# rgb2hdmi-composite-adapter.net
KiCad netlist of a schematic drawn in EAGLE
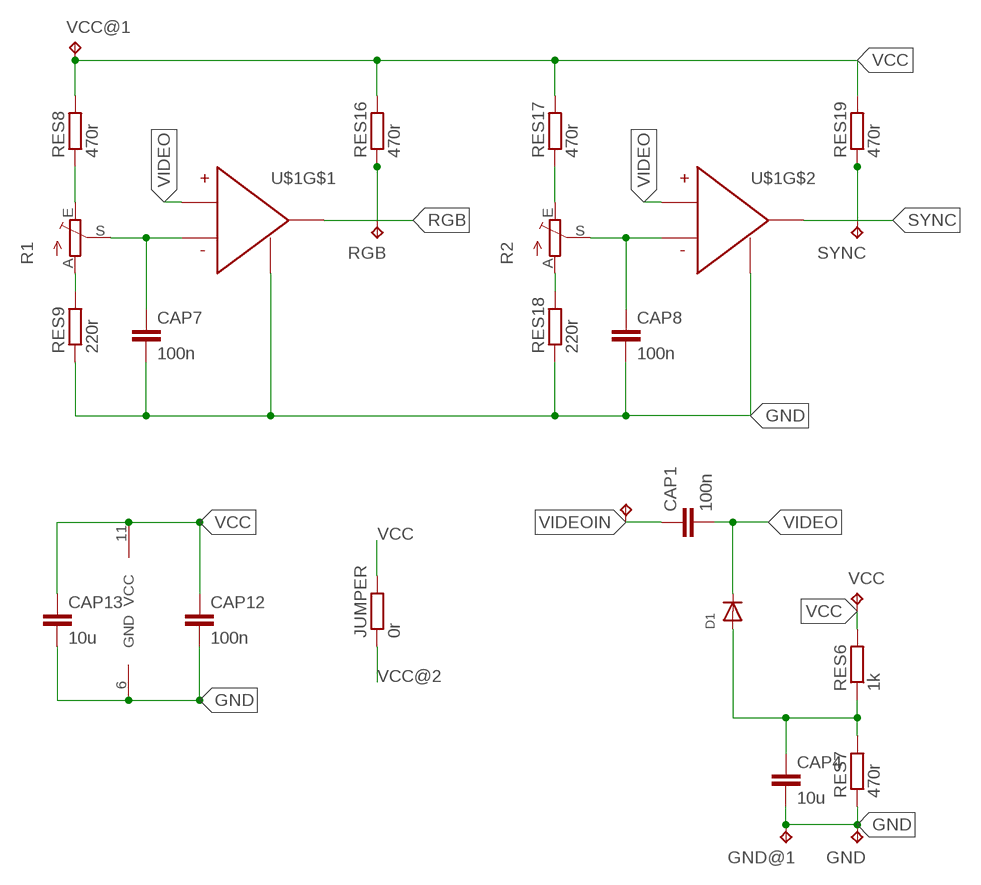
[diagram p0: schematic, sheet 1]

(export (version "E")
  (design (tool "Eeschema 10.0.6"))
  (components
    (comp (ref "CAP1")
      (value "100n")
      (footprint "eagle-import:C025-025X050")
      (libsource (lib "eagle-import") (part "C-EU025-025X050"))
    )
    (comp (ref "CAP4")
      (value "10u")
      (footprint "eagle-import:C025-025X050")
      (libsource (lib "eagle-import") (part "C-EU025-025X050"))
    )
    (comp (ref "CAP7")
      (value "100n")
      (footprint "eagle-import:C025-025X050")
      (libsource (lib "eagle-import") (part "C-EU025-025X050"))
    )
    (comp (ref "CAP8")
      (value "100n")
      (footprint "eagle-import:C025-025X050")
      (libsource (lib "eagle-import") (part "C-EU025-025X050"))
    )
    (comp (ref "CAP12")
      (value "100n")
      (footprint "eagle-import:C025-025X050")
      (libsource (lib "eagle-import") (part "C-EU025-025X050"))
    )
    (comp (ref "CAP13")
      (value "10u")
      (footprint "eagle-import:C025-025X050")
      (libsource (lib "eagle-import") (part "C-EU025-025X050"))
    )
    (comp (ref "D1")
      (value "DIODEDO-1N4148")
      (footprint "eagle-import:DO-1N4148")
      (libsource (lib "eagle-import") (part "DIODEDO-1N4148"))
    )
    (comp (ref "GND")
      (value "TPPAD1-17Y")
      (footprint "eagle-import:P1-17Y")
      (libsource (lib "eagle-import") (part "TPPAD1-17Y"))
    )
    (comp (ref "GND@1")
      (value "TPPAD1-17Y")
      (footprint "eagle-import:P1-17Y")
      (libsource (lib "eagle-import") (part "TPPAD1-17Y"))
    )
    (comp (ref "JUMPER")
      (value "0r")
      (footprint "eagle-import:0207_10")
      (libsource (lib "eagle-import") (part "R-EU_0207/10"))
    )
    (comp (ref "R1")
      (value "TRIM_EU-B64Y")
      (footprint "eagle-import:B64Y")
      (libsource (lib "eagle-import") (part "TRIM_EU-B64Y"))
    )
    (comp (ref "R2")
      (value "TRIM_EU-B64Y")
      (footprint "eagle-import:B64Y")
      (libsource (lib "eagle-import") (part "TRIM_EU-B64Y"))
    )
    (comp (ref "RES6")
      (value "1k")
      (footprint "eagle-import:0207_10")
      (libsource (lib "eagle-import") (part "R-EU_0207/10"))
    )
    (comp (ref "RES7")
      (value "470r")
      (footprint "eagle-import:0207_10")
      (libsource (lib "eagle-import") (part "R-EU_0207/10"))
    )
    (comp (ref "RES8")
      (value "470r")
      (footprint "eagle-import:0207_10")
      (libsource (lib "eagle-import") (part "R-EU_0207/10"))
    )
    (comp (ref "RES9")
      (value "220r")
      (footprint "eagle-import:0207_10")
      (libsource (lib "eagle-import") (part "R-EU_0207/10"))
    )
    (comp (ref "RES16")
      (value "470r")
      (footprint "eagle-import:0207_10")
      (libsource (lib "eagle-import") (part "R-EU_0207/10"))
    )
    (comp (ref "RES17")
      (value "470r")
      (footprint "eagle-import:0207_10")
      (libsource (lib "eagle-import") (part "R-EU_0207/10"))
    )
    (comp (ref "RES18")
      (value "220r")
      (footprint "eagle-import:0207_10")
      (libsource (lib "eagle-import") (part "R-EU_0207/10"))
    )
    (comp (ref "RES19")
      (value "470r")
      (footprint "eagle-import:0207_10")
      (libsource (lib "eagle-import") (part "R-EU_0207/10"))
    )
    (comp (ref "RGB")
      (value "TPPAD1-17Y")
      (footprint "eagle-import:P1-17Y")
      (libsource (lib "eagle-import") (part "TPPAD1-17Y"))
    )
    (comp (ref "SYNC")
      (value "TPPAD1-17Y")
      (footprint "eagle-import:P1-17Y")
      (libsource (lib "eagle-import") (part "TPPAD1-17Y"))
    )
    (comp (ref "U$1")
      (value "LM319PROPER-DIL-14")
      (footprint "eagle-import:DIL14")
      (libsource (lib "eagle-import") (part "LM319PROPER-DIL-14"))
    )
    (comp (ref "VCC")
      (value "TPPAD1-17Y")
      (footprint "eagle-import:P1-17Y")
      (libsource (lib "eagle-import") (part "TPPAD1-17Y"))
    )
    (comp (ref "VCC@1")
      (value "TPPAD1-17Y")
      (footprint "eagle-import:P1-17Y")
      (libsource (lib "eagle-import") (part "TPPAD1-17Y"))
    )
    (comp (ref "VIDEOIN")
      (value "TPPAD1-17Y")
      (footprint "eagle-import:P1-17Y")
      (libsource (lib "eagle-import") (part "TPPAD1-17Y"))
    )
  )
  (nets
    (net (code "1") (name "/VCC@2") (class "Default")
      (node (ref "JUMPER") (pin "1") (pinfunction "1_1") (pintype "passive"))
    )
    (net (code "2") (name "GND") (class "Default")
      (node (ref "CAP12") (pin "2") (pinfunction "2_2") (pintype "passive"))
      (node (ref "CAP13") (pin "2") (pinfunction "2_2") (pintype "passive"))
      (node (ref "CAP4") (pin "2") (pinfunction "2_2") (pintype "passive"))
      (node (ref "CAP7") (pin "2") (pinfunction "2_2") (pintype "passive"))
      (node (ref "CAP8") (pin "2") (pinfunction "2_2") (pintype "passive"))
      (node (ref "GND") (pin "TP") (pinfunction "TP_TP") (pintype "input"))
      (node (ref "GND@1") (pin "TP") (pinfunction "TP_TP") (pintype "input"))
      (node (ref "RES18") (pin "1") (pinfunction "1_1") (pintype "passive"))
      (node (ref "RES7") (pin "1") (pinfunction "1_1") (pintype "passive"))
      (node (ref "RES9") (pin "1") (pinfunction "1_1") (pintype "passive"))
      (node (ref "U$1") (pin "3") (pinfunction "GND_3") (pintype "power_in"))
      (node (ref "U$1") (pin "6") (pinfunction "GND_6") (pintype "power_in"))
      (node (ref "U$1") (pin "8") (pinfunction "GND_8") (pintype "power_in"))
    )
    (net (code "3") (name "Net-(CAP4-Pad1)") (class "Default")
      (node (ref "CAP4") (pin "1") (pinfunction "1_1") (pintype "passive"))
      (node (ref "D1") (pin "A") (pinfunction "A_A") (pintype "passive"))
      (node (ref "RES6") (pin "1") (pinfunction "1_1") (pintype "passive"))
      (node (ref "RES7") (pin "2") (pinfunction "2_2") (pintype "passive"))
    )
    (net (code "4") (name "Net-(R1-PadA)") (class "Default")
      (node (ref "R1") (pin "A") (pinfunction "A_A") (pintype "passive"))
      (node (ref "RES9") (pin "2") (pinfunction "2_2") (pintype "passive"))
    )
    (net (code "5") (name "Net-(R1-PadE)") (class "Default")
      (node (ref "R1") (pin "E") (pinfunction "E_E") (pintype "passive"))
      (node (ref "RES8") (pin "1") (pinfunction "1_1") (pintype "passive"))
    )
    (net (code "6") (name "Net-(R2-PadA)") (class "Default")
      (node (ref "R2") (pin "A") (pinfunction "A_A") (pintype "passive"))
      (node (ref "RES18") (pin "2") (pinfunction "2_2") (pintype "passive"))
    )
    (net (code "7") (name "Net-(R2-PadE)") (class "Default")
      (node (ref "R2") (pin "E") (pinfunction "E_E") (pintype "passive"))
      (node (ref "RES17") (pin "1") (pinfunction "1_1") (pintype "passive"))
    )
    (net (code "8") (name "Net-(U$1A-INV)") (class "Default")
      (node (ref "CAP7") (pin "1") (pinfunction "1_1") (pintype "passive"))
      (node (ref "R1") (pin "S") (pinfunction "S_S") (pintype "passive"))
      (node (ref "U$1") (pin "5") (pinfunction "INV_5") (pintype "bidirectional"))
    )
    (net (code "9") (name "Net-(U$1B-INV)") (class "Default")
      (node (ref "CAP8") (pin "1") (pinfunction "1_1") (pintype "passive"))
      (node (ref "R2") (pin "S") (pinfunction "S_S") (pintype "passive"))
      (node (ref "U$1") (pin "10") (pinfunction "INV_10") (pintype "bidirectional"))
    )
    (net (code "10") (name "RGB") (class "Default")
      (node (ref "RES16") (pin "1") (pinfunction "1_1") (pintype "passive"))
      (node (ref "RGB") (pin "TP") (pinfunction "TP_TP") (pintype "input"))
      (node (ref "U$1") (pin "12") (pinfunction "OUT_12") (pintype "bidirectional"))
    )
    (net (code "11") (name "SYNC") (class "Default")
      (node (ref "RES19") (pin "1") (pinfunction "1_1") (pintype "passive"))
      (node (ref "SYNC") (pin "TP") (pinfunction "TP_TP") (pintype "input"))
      (node (ref "U$1") (pin "7") (pinfunction "OUT_7") (pintype "bidirectional"))
    )
    (net (code "12") (name "VCC") (class "Default")
      (node (ref "CAP12") (pin "1") (pinfunction "1_1") (pintype "passive"))
      (node (ref "CAP13") (pin "1") (pinfunction "1_1") (pintype "passive"))
      (node (ref "JUMPER") (pin "2") (pinfunction "2_2") (pintype "passive"))
      (node (ref "RES16") (pin "2") (pinfunction "2_2") (pintype "passive"))
      (node (ref "RES17") (pin "2") (pinfunction "2_2") (pintype "passive"))
      (node (ref "RES19") (pin "2") (pinfunction "2_2") (pintype "passive"))
      (node (ref "RES6") (pin "2") (pinfunction "2_2") (pintype "passive"))
      (node (ref "RES8") (pin "2") (pinfunction "2_2") (pintype "passive"))
      (node (ref "U$1") (pin "11") (pinfunction "VCC_11") (pintype "power_in"))
      (node (ref "VCC") (pin "TP") (pinfunction "TP_TP") (pintype "input"))
      (node (ref "VCC@1") (pin "TP") (pinfunction "TP_TP") (pintype "input"))
    )
    (net (code "13") (name "VIDEO") (class "Default")
      (node (ref "CAP1") (pin "2") (pinfunction "2_2") (pintype "passive"))
      (node (ref "D1") (pin "C") (pinfunction "C_C") (pintype "passive"))
      (node (ref "U$1") (pin "4") (pinfunction "NONINV_4") (pintype "bidirectional"))
      (node (ref "U$1") (pin "9") (pinfunction "NONINV_9") (pintype "bidirectional"))
    )
    (net (code "14") (name "VIDEOIN") (class "Default")
      (node (ref "CAP1") (pin "1") (pinfunction "1_1") (pintype "passive"))
      (node (ref "VIDEOIN") (pin "TP") (pinfunction "TP_TP") (pintype "input"))
    )
  )
)
